# humidity_sensor.net
KiCad netlist of a schematic drawn in EAGLE
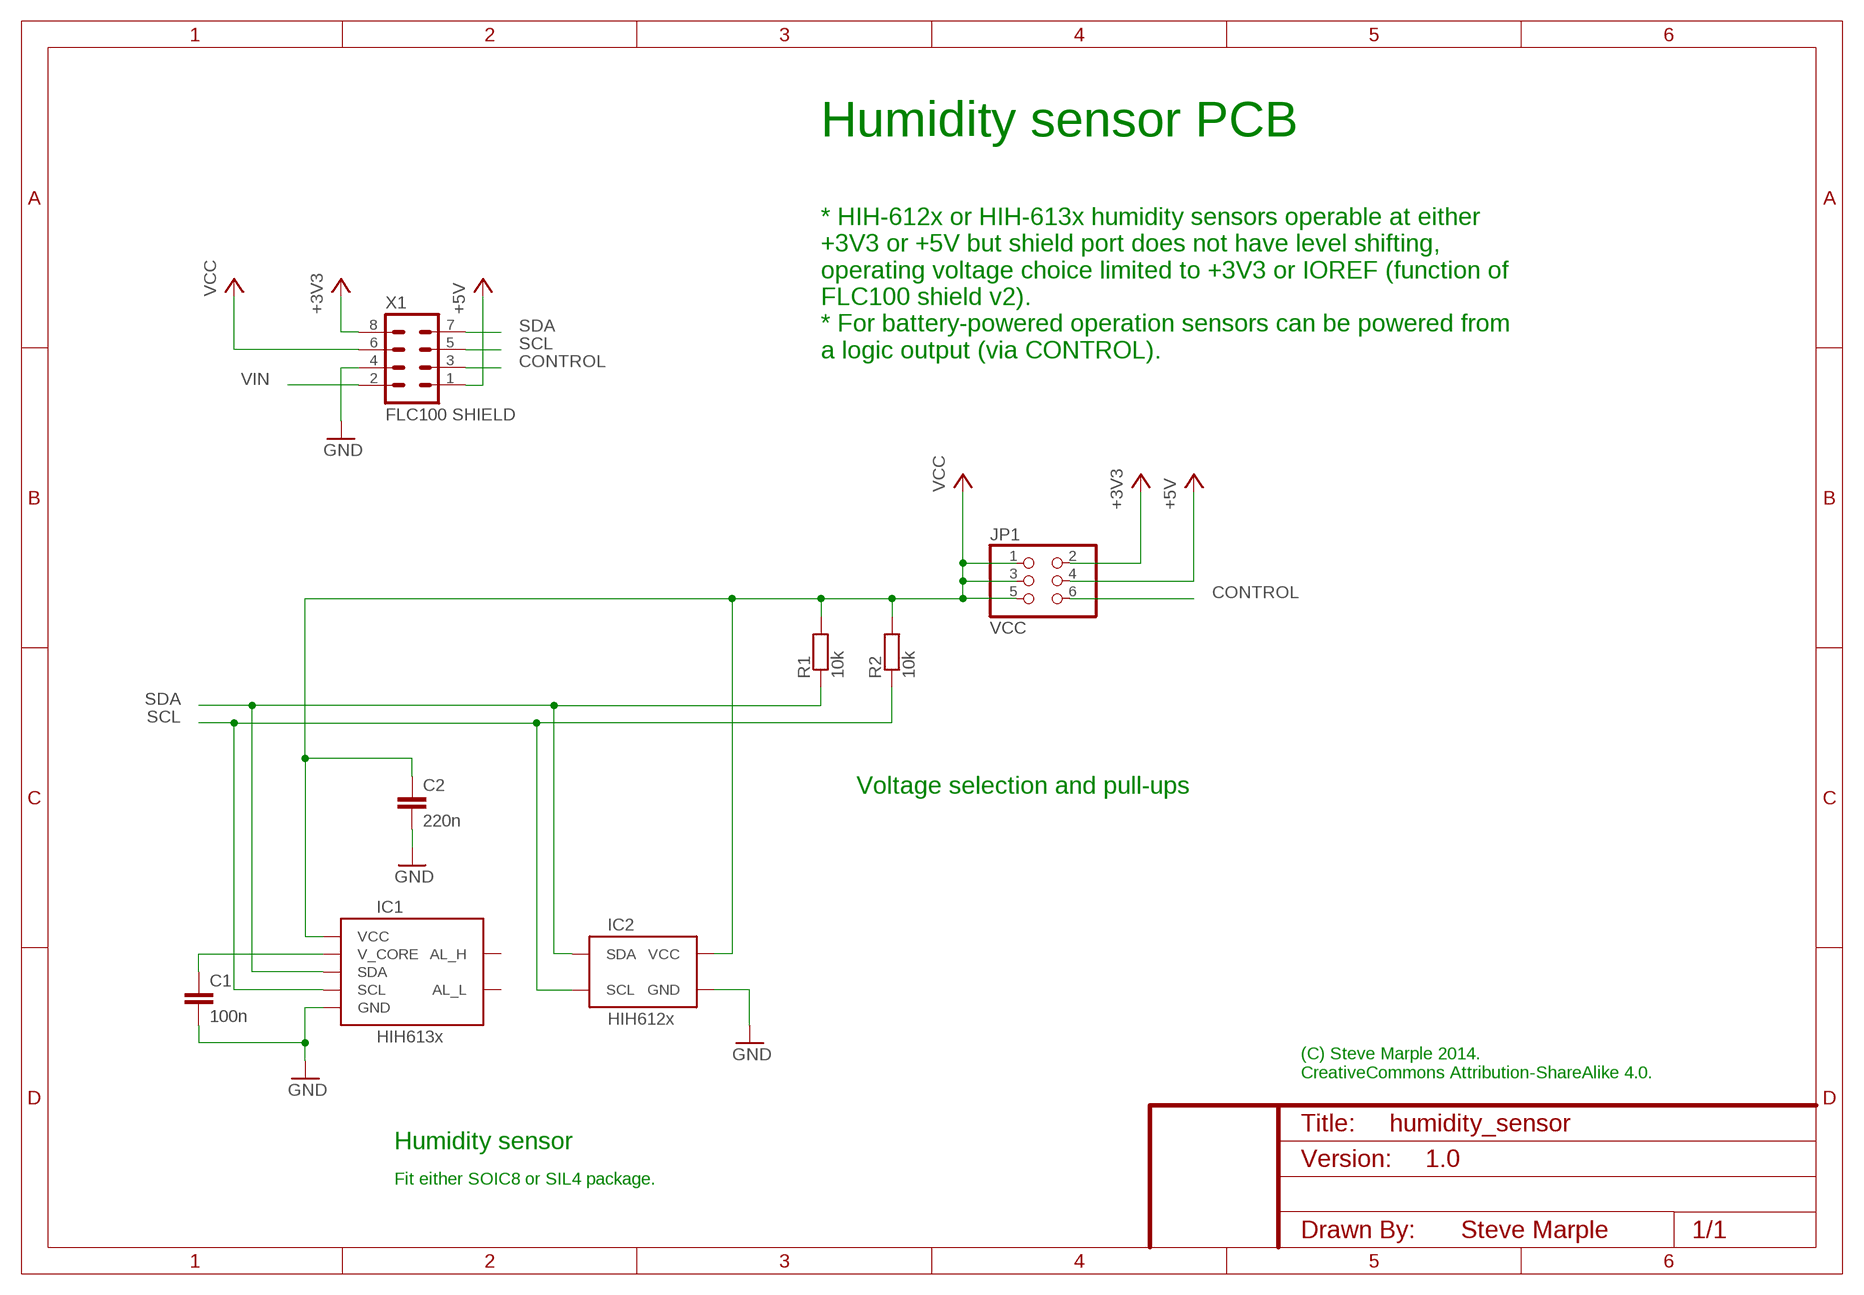
[diagram p0: schematic, sheet 1]

(export (version "E")
  (design (tool "Eeschema 10.0.6"))
  (components
    (comp (ref "C1")
      (value "100n")
      (footprint "eagle-import:CAP-PTH-SMALL")
      (libsource (lib "eagle-import") (part "CAPPTH"))
    )
    (comp (ref "C2")
      (value "220n")
      (footprint "eagle-import:CAP-PTH-SMALL")
      (libsource (lib "eagle-import") (part "CAPPTH"))
    )
    (comp (ref "IC1")
      (value "HIH613x")
      (footprint "eagle-import:SO08")
      (libsource (lib "eagle-import") (part "HONEYWELL-HIH613XSOIC8"))
    )
    (comp (ref "IC2")
      (value "HIH612x")
      (footprint "eagle-import:SIL04")
      (libsource (lib "eagle-import") (part "HONEYWELL-HIH612X"))
    )
    (comp (ref "JP1")
      (value "VCC")
      (footprint "eagle-import:2X03")
      (libsource (lib "eagle-import") (part "PINHD-2X3"))
    )
    (comp (ref "R1")
      (value "10k")
      (footprint "eagle-import:RES-AXIAL-0.4")
      (libsource (lib "eagle-import") (part "RESISTOR"))
    )
    (comp (ref "R2")
      (value "10k")
      (footprint "eagle-import:RES-AXIAL-0.4")
      (libsource (lib "eagle-import") (part "RESISTOR"))
    )
    (comp (ref "X1")
      (value "FLC100 SHIELD")
      (footprint "eagle-import:ML8")
      (libsource (lib "eagle-import") (part "ML8"))
    )
  )
  (nets
    (net (code "1") (name "+3V3") (class "Default")
      (node (ref "JP1") (pin "2") (pinfunction "2_2") (pintype "passive"))
      (node (ref "X1") (pin "8") (pinfunction "8_8") (pintype "passive"))
    )
    (net (code "2") (name "+5V") (class "Default")
      (node (ref "JP1") (pin "4") (pinfunction "4_4") (pintype "passive"))
      (node (ref "X1") (pin "1") (pinfunction "1_1") (pintype "passive"))
    )
    (net (code "3") (name "/CONTROL") (class "Default")
      (node (ref "JP1") (pin "6") (pinfunction "6_6") (pintype "passive"))
      (node (ref "X1") (pin "3") (pinfunction "3_3") (pintype "passive"))
    )
    (net (code "4") (name "/SCL") (class "Default")
      (node (ref "IC1") (pin "3") (pinfunction "SCL_3") (pintype "bidirectional"))
      (node (ref "IC2") (pin "3") (pinfunction "SCL_3") (pintype "bidirectional"))
      (node (ref "R2") (pin "P$1") (pinfunction "1_P$1") (pintype "passive"))
      (node (ref "X1") (pin "5") (pinfunction "5_5") (pintype "passive"))
    )
    (net (code "5") (name "/SDA") (class "Default")
      (node (ref "IC1") (pin "4") (pinfunction "SDA_4") (pintype "bidirectional"))
      (node (ref "IC2") (pin "4") (pinfunction "SDA_4") (pintype "bidirectional"))
      (node (ref "R1") (pin "P$1") (pinfunction "1_P$1") (pintype "passive"))
      (node (ref "X1") (pin "7") (pinfunction "7_7") (pintype "passive"))
    )
    (net (code "6") (name "/VIN") (class "Default")
      (node (ref "X1") (pin "2") (pinfunction "2_2") (pintype "passive"))
    )
    (net (code "7") (name "GND") (class "Default")
      (node (ref "C1") (pin "2") (pinfunction "2_2") (pintype "passive"))
      (node (ref "C2") (pin "2") (pinfunction "2_2") (pintype "passive"))
      (node (ref "IC1") (pin "2") (pinfunction "GND_2") (pintype "power_in"))
      (node (ref "IC2") (pin "2") (pinfunction "GND_2") (pintype "power_in"))
      (node (ref "X1") (pin "4") (pinfunction "4_4") (pintype "passive"))
    )
    (net (code "8") (name "Net-(IC1-V_CORE)") (class "Default")
      (node (ref "C1") (pin "1") (pinfunction "1_1") (pintype "passive"))
      (node (ref "IC1") (pin "1") (pinfunction "V_CORE_1") (pintype "output"))
    )
    (net (code "9") (name "VCC") (class "Default")
      (node (ref "C2") (pin "1") (pinfunction "1_1") (pintype "passive"))
      (node (ref "IC1") (pin "8") (pinfunction "VCC_8") (pintype "power_in"))
      (node (ref "IC2") (pin "1") (pinfunction "VCC_1") (pintype "power_in"))
      (node (ref "JP1") (pin "1") (pinfunction "1_1") (pintype "passive"))
      (node (ref "JP1") (pin "3") (pinfunction "3_3") (pintype "passive"))
      (node (ref "JP1") (pin "5") (pinfunction "5_5") (pintype "passive"))
      (node (ref "R1") (pin "P$2") (pinfunction "2_P$2") (pintype "passive"))
      (node (ref "R2") (pin "P$2") (pinfunction "2_P$2") (pintype "passive"))
      (node (ref "X1") (pin "6") (pinfunction "6_6") (pintype "passive"))
    )
    (net (code "10") (name "unconnected-(IC1-AL_H-Pad5)") (class "Default")
      (node (ref "IC1") (pin "5") (pinfunction "AL_H_5") (pintype "bidirectional"))
    )
    (net (code "11") (name "unconnected-(IC1-AL_L-Pad6)") (class "Default")
      (node (ref "IC1") (pin "6") (pinfunction "AL_L_6") (pintype "bidirectional"))
    )
  )
)
